# SFH_2430_Breakout.net
KiCad netlist of a schematic drawn in EAGLE
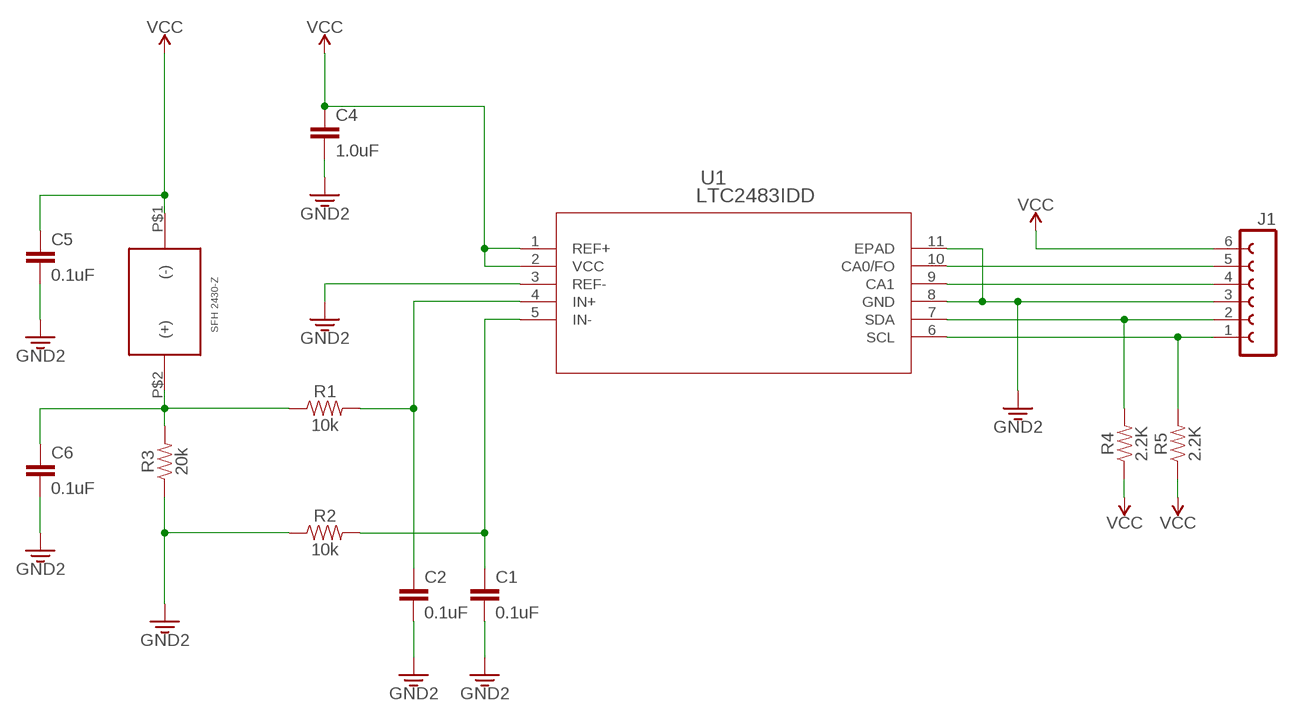
[diagram p0: schematic, sheet 1]

(export (version "E")
  (design (tool "Eeschema 10.0.6"))
  (components
    (comp (ref "C1")
      (value "0.1uF")
      (footprint "eagle-import:0603")
      (libsource (lib "eagle-import") (part "0.1UF-0603-25V-5%"))
    )
    (comp (ref "C2")
      (value "0.1uF")
      (footprint "eagle-import:0603")
      (libsource (lib "eagle-import") (part "0.1UF-0603-25V-5%"))
    )
    (comp (ref "C4")
      (value "1.0uF")
      (footprint "eagle-import:0805")
      (libsource (lib "eagle-import") (part "1.0UF-0805-25V-10%"))
    )
    (comp (ref "C5")
      (value "0.1uF")
      (footprint "eagle-import:0603")
      (libsource (lib "eagle-import") (part "0.1UF-0603-100V-10%"))
    )
    (comp (ref "C6")
      (value "0.1uF")
      (footprint "eagle-import:0603")
      (libsource (lib "eagle-import") (part "0.1UF-0603-100V-10%"))
    )
    (comp (ref "J1")
      (value "FE06-1")
      (footprint "eagle-import:FE06")
      (libsource (lib "eagle-import") (part "FE06-1"))
    )
    (comp (ref "R1")
      (value "10k")
      (footprint "eagle-import:0805")
      (libsource (lib "eagle-import") (part "RESISTOR0805"))
    )
    (comp (ref "R2")
      (value "10k")
      (footprint "eagle-import:0805")
      (libsource (lib "eagle-import") (part "RESISTOR0805"))
    )
    (comp (ref "R3")
      (value "20k")
      (footprint "eagle-import:0805")
      (libsource (lib "eagle-import") (part "RESISTOR0805"))
    )
    (comp (ref "R4")
      (value "2.2K")
      (footprint "eagle-import:0805")
      (libsource (lib "eagle-import") (part "RESISTOR0805"))
    )
    (comp (ref "R5")
      (value "2.2K")
      (footprint "eagle-import:0805")
      (libsource (lib "eagle-import") (part "RESISTOR0805"))
    )
    (comp (ref "U$1")
      (value "SFH-2430-Z")
      (footprint "eagle-import:DIL")
      (libsource (lib "eagle-import") (part "SFH-2430-Z"))
    )
    (comp (ref "U1")
      (value "LTC2483IDD")
      (footprint "eagle-import:DFN-10_DD")
      (fields (field (name "MANUFACTURER_PART_NUMBER") "ltc2483idd"))
      (libsource (lib "eagle-import") (part "LTC2483IDD"))
    )
  )
  (nets
    (net (code "1") (name "GND2") (class "Default")
      (node (ref "C1") (pin "2") (pinfunction "2_2") (pintype "passive"))
      (node (ref "C2") (pin "2") (pinfunction "2_2") (pintype "passive"))
      (node (ref "C4") (pin "2") (pinfunction "2_2") (pintype "passive"))
      (node (ref "C5") (pin "2") (pinfunction "2_2") (pintype "passive"))
      (node (ref "C6") (pin "2") (pinfunction "2_2") (pintype "passive"))
      (node (ref "J1") (pin "3") (pinfunction "3_3") (pintype "passive"))
      (node (ref "R2") (pin "1") (pinfunction "1_1") (pintype "passive"))
      (node (ref "R3") (pin "1") (pinfunction "1_1") (pintype "passive"))
      (node (ref "U1") (pin "11") (pinfunction "EPAD_11") (pintype "passive"))
      (node (ref "U1") (pin "3") (pinfunction "REF-_3") (pintype "input"))
      (node (ref "U1") (pin "8") (pinfunction "GND_8") (pintype "power_in"))
    )
    (net (code "2") (name "Net-(U$1-(+))") (class "Default")
      (node (ref "C6") (pin "1") (pinfunction "1_1") (pintype "passive"))
      (node (ref "R1") (pin "1") (pinfunction "1_1") (pintype "passive"))
      (node (ref "R3") (pin "2") (pinfunction "2_2") (pintype "passive"))
      (node (ref "U$1") (pin "P$2") (pinfunction "(+)_P$2") (pintype "output"))
    )
    (net (code "3") (name "Net-(U1-CA0{slash}FO)") (class "Default")
      (node (ref "J1") (pin "5") (pinfunction "5_5") (pintype "passive"))
      (node (ref "U1") (pin "10") (pinfunction "CA0/FO_10") (pintype "passive"))
    )
    (net (code "4") (name "Net-(U1-CA1)") (class "Default")
      (node (ref "J1") (pin "4") (pinfunction "4_4") (pintype "passive"))
      (node (ref "U1") (pin "9") (pinfunction "CA1_9") (pintype "passive"))
    )
    (net (code "5") (name "Net-(U1-IN+)") (class "Default")
      (node (ref "C2") (pin "1") (pinfunction "1_1") (pintype "passive"))
      (node (ref "R1") (pin "2") (pinfunction "2_2") (pintype "passive"))
      (node (ref "U1") (pin "4") (pinfunction "IN+_4") (pintype "input"))
    )
    (net (code "6") (name "Net-(U1-IN-)") (class "Default")
      (node (ref "C1") (pin "1") (pinfunction "1_1") (pintype "passive"))
      (node (ref "R2") (pin "2") (pinfunction "2_2") (pintype "passive"))
      (node (ref "U1") (pin "5") (pinfunction "IN-_5") (pintype "input"))
    )
    (net (code "7") (name "Net-(U1-SCL)") (class "Default")
      (node (ref "J1") (pin "1") (pinfunction "1_1") (pintype "passive"))
      (node (ref "R5") (pin "2") (pinfunction "2_2") (pintype "passive"))
      (node (ref "U1") (pin "6") (pinfunction "SCL_6") (pintype "passive"))
    )
    (net (code "8") (name "Net-(U1-SDA)") (class "Default")
      (node (ref "J1") (pin "2") (pinfunction "2_2") (pintype "passive"))
      (node (ref "R4") (pin "2") (pinfunction "2_2") (pintype "passive"))
      (node (ref "U1") (pin "7") (pinfunction "SDA_7") (pintype "output"))
    )
    (net (code "9") (name "VCC") (class "Default")
      (node (ref "C4") (pin "1") (pinfunction "1_1") (pintype "passive"))
      (node (ref "C5") (pin "1") (pinfunction "1_1") (pintype "passive"))
      (node (ref "J1") (pin "6") (pinfunction "6_6") (pintype "passive"))
      (node (ref "R4") (pin "1") (pinfunction "1_1") (pintype "passive"))
      (node (ref "R5") (pin "1") (pinfunction "1_1") (pintype "passive"))
      (node (ref "U$1") (pin "P$1") (pinfunction "(-)_P$1") (pintype "input"))
      (node (ref "U1") (pin "1") (pinfunction "REF+_1") (pintype "input"))
      (node (ref "U1") (pin "2") (pinfunction "VCC_2") (pintype "power_in"))
    )
  )
)
